# PW_portable.net
KiCad netlist of a schematic drawn in EAGLE
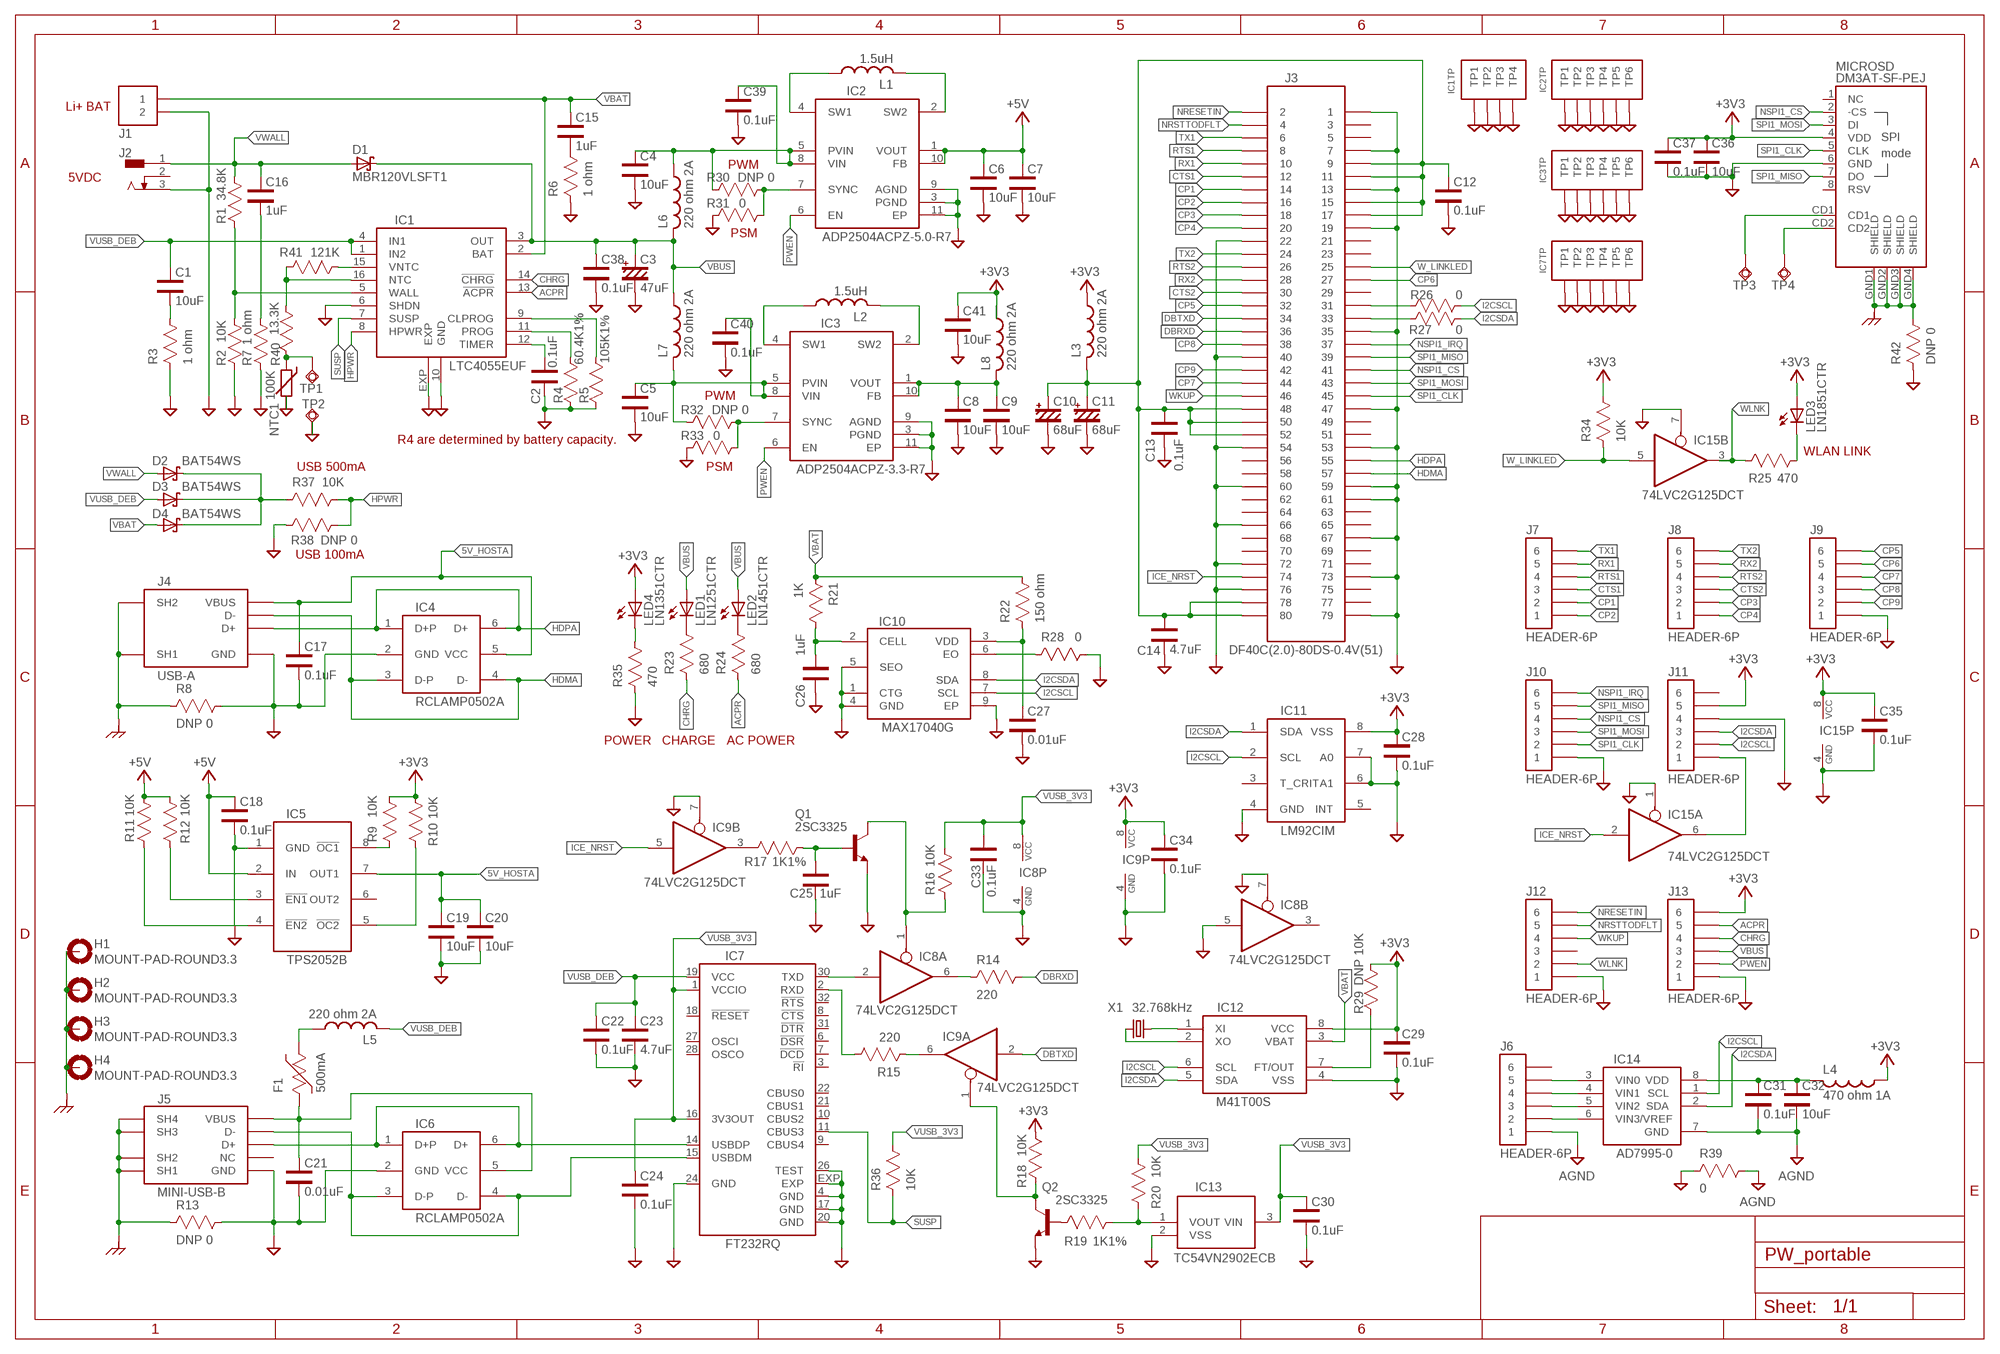
[diagram p0: schematic, sheet 1]

(export (version "E")
  (design (tool "Eeschema 10.0.6"))
  (components
    (comp (ref "C1")
      (value "10uF")
      (footprint "eagle-import:C0603")
      (libsource (lib "eagle-import") (part "C0603"))
    )
    (comp (ref "C2")
      (value "0.1uF")
      (footprint "eagle-import:C0603")
      (libsource (lib "eagle-import") (part "C0603"))
    )
    (comp (ref "C3")
      (value "47uF")
      (footprint "eagle-import:SMC_D")
      (libsource (lib "eagle-import") (part "CPSMC_D"))
    )
    (comp (ref "C4")
      (value "10uF")
      (footprint "eagle-import:C0603")
      (libsource (lib "eagle-import") (part "C0603"))
    )
    (comp (ref "C5")
      (value "10uF")
      (footprint "eagle-import:C0603")
      (libsource (lib "eagle-import") (part "C0603"))
    )
    (comp (ref "C6")
      (value "10uF")
      (footprint "eagle-import:C0603")
      (libsource (lib "eagle-import") (part "C0603"))
    )
    (comp (ref "C7")
      (value "10uF")
      (footprint "eagle-import:C0603")
      (libsource (lib "eagle-import") (part "C0603"))
    )
    (comp (ref "C8")
      (value "10uF")
      (footprint "eagle-import:C0603")
      (libsource (lib "eagle-import") (part "C0603"))
    )
    (comp (ref "C9")
      (value "10uF")
      (footprint "eagle-import:C0603")
      (libsource (lib "eagle-import") (part "C0603"))
    )
    (comp (ref "C10")
      (value "68uF")
      (footprint "eagle-import:SMC_D")
      (libsource (lib "eagle-import") (part "CPSMC_D"))
    )
    (comp (ref "C11")
      (value "68uF")
      (footprint "eagle-import:SMC_D")
      (libsource (lib "eagle-import") (part "CPSMC_D"))
    )
    (comp (ref "C12")
      (value "0.1uF")
      (footprint "eagle-import:C0603")
      (libsource (lib "eagle-import") (part "C0603"))
    )
    (comp (ref "C13")
      (value "0.1uF")
      (footprint "eagle-import:C0603")
      (libsource (lib "eagle-import") (part "C0603"))
    )
    (comp (ref "C14")
      (value "4.7uF")
      (footprint "eagle-import:C0603")
      (libsource (lib "eagle-import") (part "C0603"))
    )
    (comp (ref "C15")
      (value "1uF")
      (footprint "eagle-import:C0603")
      (libsource (lib "eagle-import") (part "C0603"))
    )
    (comp (ref "C16")
      (value "1uF")
      (footprint "eagle-import:C0603")
      (libsource (lib "eagle-import") (part "C0603"))
    )
    (comp (ref "C17")
      (value "0.1uF")
      (footprint "eagle-import:C0603")
      (libsource (lib "eagle-import") (part "C0603"))
    )
    (comp (ref "C18")
      (value "0.1uF")
      (footprint "eagle-import:C0603")
      (libsource (lib "eagle-import") (part "C0603"))
    )
    (comp (ref "C19")
      (value "10uF")
      (footprint "eagle-import:C0603")
      (libsource (lib "eagle-import") (part "C0603"))
    )
    (comp (ref "C20")
      (value "10uF")
      (footprint "eagle-import:C0603")
      (libsource (lib "eagle-import") (part "C0603"))
    )
    (comp (ref "C21")
      (value "0.01uF")
      (footprint "eagle-import:C0603")
      (libsource (lib "eagle-import") (part "C0603"))
    )
    (comp (ref "C22")
      (value "0.1uF")
      (footprint "eagle-import:C0603")
      (libsource (lib "eagle-import") (part "C0603"))
    )
    (comp (ref "C23")
      (value "4.7uF")
      (footprint "eagle-import:C0603")
      (libsource (lib "eagle-import") (part "C0603"))
    )
    (comp (ref "C24")
      (value "0.1uF")
      (footprint "eagle-import:C0603")
      (libsource (lib "eagle-import") (part "C0603"))
    )
    (comp (ref "C25")
      (value "1uF")
      (footprint "eagle-import:C0603")
      (libsource (lib "eagle-import") (part "C0603"))
    )
    (comp (ref "C26")
      (value "1uF")
      (footprint "eagle-import:C0603")
      (libsource (lib "eagle-import") (part "C0603"))
    )
    (comp (ref "C27")
      (value "0.01uF")
      (footprint "eagle-import:C0603")
      (libsource (lib "eagle-import") (part "C0603"))
    )
    (comp (ref "C28")
      (value "0.1uF")
      (footprint "eagle-import:C0603")
      (libsource (lib "eagle-import") (part "C0603"))
    )
    (comp (ref "C29")
      (value "0.1uF")
      (footprint "eagle-import:C0603")
      (libsource (lib "eagle-import") (part "C0603"))
    )
    (comp (ref "C30")
      (value "0.1uF")
      (footprint "eagle-import:C0603")
      (libsource (lib "eagle-import") (part "C0603"))
    )
    (comp (ref "C31")
      (value "0.1uF")
      (footprint "eagle-import:C0603")
      (libsource (lib "eagle-import") (part "C0603"))
    )
    (comp (ref "C32")
      (value "10uF")
      (footprint "eagle-import:C0603")
      (libsource (lib "eagle-import") (part "C0603"))
    )
    (comp (ref "C33")
      (value "0.1uF")
      (footprint "eagle-import:C0603")
      (libsource (lib "eagle-import") (part "C0603"))
    )
    (comp (ref "C34")
      (value "0.1uF")
      (footprint "eagle-import:C0603")
      (libsource (lib "eagle-import") (part "C0603"))
    )
    (comp (ref "C35")
      (value "0.1uF")
      (footprint "eagle-import:C0603")
      (libsource (lib "eagle-import") (part "C0603"))
    )
    (comp (ref "C36")
      (value "10uF")
      (footprint "eagle-import:C0603")
      (libsource (lib "eagle-import") (part "C0603"))
    )
    (comp (ref "C37")
      (value "0.1uF")
      (footprint "eagle-import:C0603")
      (libsource (lib "eagle-import") (part "C0603"))
    )
    (comp (ref "C38")
      (value "0.1uF")
      (footprint "eagle-import:C0603")
      (libsource (lib "eagle-import") (part "C0603"))
    )
    (comp (ref "C39")
      (value "0.1uF")
      (footprint "eagle-import:C0603")
      (libsource (lib "eagle-import") (part "C0603"))
    )
    (comp (ref "C40")
      (value "0.1uF")
      (footprint "eagle-import:C0603")
      (libsource (lib "eagle-import") (part "C0603"))
    )
    (comp (ref "C41")
      (value "10uF")
      (footprint "eagle-import:C0603")
      (libsource (lib "eagle-import") (part "C0603"))
    )
    (comp (ref "D1")
      (value "MBR120VLSFT1")
      (footprint "eagle-import:SOD123FL")
      (libsource (lib "eagle-import") (part "MBR120VLSFT1"))
    )
    (comp (ref "D2")
      (value "BAT54WS")
      (footprint "eagle-import:SOD323")
      (libsource (lib "eagle-import") (part "BAT54WS"))
    )
    (comp (ref "D3")
      (value "BAT54WS")
      (footprint "eagle-import:SOD323")
      (libsource (lib "eagle-import") (part "BAT54WS"))
    )
    (comp (ref "D4")
      (value "BAT54WS")
      (footprint "eagle-import:SOD323")
      (libsource (lib "eagle-import") (part "BAT54WS"))
    )
    (comp (ref "F1")
      (value "500mA")
      (footprint "eagle-import:P1206")
      (libsource (lib "eagle-import") (part "NANOSMDC050F/13"))
    )
    (comp (ref "H1")
      (value "MOUNT-PAD-ROUND3.3")
      (footprint "eagle-import:3,3-PAD")
      (libsource (lib "eagle-import") (part "MOUNT-PAD-ROUND3.3"))
    )
    (comp (ref "H2")
      (value "MOUNT-PAD-ROUND3.3")
      (footprint "eagle-import:3,3-PAD")
      (libsource (lib "eagle-import") (part "MOUNT-PAD-ROUND3.3"))
    )
    (comp (ref "H3")
      (value "MOUNT-PAD-ROUND3.3")
      (footprint "eagle-import:3,3-PAD")
      (libsource (lib "eagle-import") (part "MOUNT-PAD-ROUND3.3"))
    )
    (comp (ref "H4")
      (value "MOUNT-PAD-ROUND3.3")
      (footprint "eagle-import:3,3-PAD")
      (libsource (lib "eagle-import") (part "MOUNT-PAD-ROUND3.3"))
    )
    (comp (ref "IC1")
      (value "LTC4055EUF")
      (footprint "eagle-import:QFN16-4X4")
      (libsource (lib "eagle-import") (part "LTC4055EUF"))
    )
    (comp (ref "IC2")
      (value "ADP2504ACPZ-5.0-R7")
      (footprint "eagle-import:LFCSP_WD-CP-10-9")
      (libsource (lib "eagle-import") (part "ADP2504ACPZ-?-R75.0"))
    )
    (comp (ref "IC3")
      (value "ADP2504ACPZ-3.3-R7")
      (footprint "eagle-import:LFCSP_WD-CP-10-9")
      (libsource (lib "eagle-import") (part "ADP2504ACPZ-?-R73.3"))
    )
    (comp (ref "IC4")
      (value "RCLAMP0502A")
      (footprint "eagle-import:SOT666")
      (libsource (lib "eagle-import") (part "RCLAMP0502A"))
    )
    (comp (ref "IC5")
      (value "TPS2052B")
      (footprint "eagle-import:D_R-PDSO-G08")
      (libsource (lib "eagle-import") (part "TPS2052B"))
    )
    (comp (ref "IC6")
      (value "RCLAMP0502A")
      (footprint "eagle-import:SOT666")
      (libsource (lib "eagle-import") (part "RCLAMP0502A"))
    )
    (comp (ref "IC7")
      (value "FT232RQ")
      (footprint "eagle-import:QFN32")
      (libsource (lib "eagle-import") (part "FT232RQ"))
    )
    (comp (ref "IC8")
      (value "74LVC2G125DCT")
      (footprint "eagle-import:SSOP08")
      (libsource (lib "eagle-import") (part "742G125DCTLVC"))
    )
    (comp (ref "IC9")
      (value "74LVC2G125DCT")
      (footprint "eagle-import:SSOP08")
      (libsource (lib "eagle-import") (part "742G125DCTLVC"))
    )
    (comp (ref "IC10")
      (value "MAX17040G")
      (footprint "eagle-import:8-TDFN")
      (libsource (lib "eagle-import") (part "MAX17040G"))
    )
    (comp (ref "IC11")
      (value "LM92CIM")
      (footprint "eagle-import:SO08")
      (libsource (lib "eagle-import") (part "LM92CIM"))
    )
    (comp (ref "IC12")
      (value "M41T00S")
      (footprint "eagle-import:SO08")
      (libsource (lib "eagle-import") (part "M41T00S"))
    )
    (comp (ref "IC13")
      (value "TC54VN2902ECB")
      (footprint "eagle-import:SOT23")
      (libsource (lib "eagle-import") (part "TC54VN02E?CB29"))
    )
    (comp (ref "IC14")
      (value "AD7995-0")
      (footprint "eagle-import:SOT23-8")
      (libsource (lib "eagle-import") (part "AD799-05"))
    )
    (comp (ref "IC15")
      (value "74LVC2G125DCT")
      (footprint "eagle-import:SSOP08")
      (libsource (lib "eagle-import") (part "742G125DCTLVC"))
    )
    (comp (ref "J1")
      (value "JACK-JST-2P-PW'SMD'")
      (footprint "eagle-import:JST-SMD-2.0")
      (libsource (lib "eagle-import") (part "JACK-JST-2P-PW'SMD'"))
    )
    (comp (ref "J2")
      (value "DCJ0202")
      (footprint "eagle-import:DCJ0202")
      (libsource (lib "eagle-import") (part "DCJ0202"))
    )
    (comp (ref "J3")
      (value "DF40C(2.0)-80DS-0.4V(51)")
      (footprint "eagle-import:DF40C(2.0)-80DS-0.4V(51)")
      (libsource (lib "eagle-import") (part "DF40C(2.0)-80DS-0.4V(51)"))
    )
    (comp (ref "J4")
      (value "USB-A")
      (footprint "eagle-import:USB-A")
      (libsource (lib "eagle-import") (part "USB-AL"))
    )
    (comp (ref "J5")
      (value "MINI-USB-B")
      (footprint "eagle-import:1734035-2")
      (libsource (lib "eagle-import") (part "MINI-USB-B"))
    )
    (comp (ref "J6")
      (value "HEADER-6P")
      (footprint "eagle-import:6P-2.54")
      (libsource (lib "eagle-import") (part "HEADER-6P"))
    )
    (comp (ref "J7")
      (value "HEADER-6P")
      (footprint "eagle-import:6P-2.54")
      (libsource (lib "eagle-import") (part "HEADER-6P"))
    )
    (comp (ref "J8")
      (value "HEADER-6P")
      (footprint "eagle-import:6P-2.54")
      (libsource (lib "eagle-import") (part "HEADER-6P"))
    )
    (comp (ref "J9")
      (value "HEADER-6P")
      (footprint "eagle-import:6P-2.54")
      (libsource (lib "eagle-import") (part "HEADER-6P"))
    )
    (comp (ref "J10")
      (value "HEADER-6P")
      (footprint "eagle-import:6P-2.54")
      (libsource (lib "eagle-import") (part "HEADER-6P"))
    )
    (comp (ref "J11")
      (value "HEADER-6P")
      (footprint "eagle-import:6P-2.54")
      (libsource (lib "eagle-import") (part "HEADER-6P"))
    )
    (comp (ref "J12")
      (value "HEADER-6P")
      (footprint "eagle-import:6P-2.54")
      (libsource (lib "eagle-import") (part "HEADER-6P"))
    )
    (comp (ref "J13")
      (value "HEADER-6P")
      (footprint "eagle-import:6P-2.54")
      (libsource (lib "eagle-import") (part "HEADER-6P"))
    )
    (comp (ref "L1")
      (value "1.5uH")
      (footprint "eagle-import:L1008")
      (libsource (lib "eagle-import") (part "LQM2HPN1R5MG0L"))
    )
    (comp (ref "L2")
      (value "1.5uH")
      (footprint "eagle-import:L1008")
      (libsource (lib "eagle-import") (part "LQM2HPN1R5MG0L"))
    )
    (comp (ref "L3")
      (value "220 ohm 2A")
      (footprint "eagle-import:L0603")
      (libsource (lib "eagle-import") (part "BLM?PG18"))
    )
    (comp (ref "L4")
      (value "470 ohm 1A")
      (footprint "eagle-import:L0603")
      (libsource (lib "eagle-import") (part "BLM?PG18"))
    )
    (comp (ref "L5")
      (value "220 ohm 2A")
      (footprint "eagle-import:L0603")
      (libsource (lib "eagle-import") (part "BLM?PG18"))
    )
    (comp (ref "L6")
      (value "220 ohm 2A")
      (footprint "eagle-import:L0603")
      (libsource (lib "eagle-import") (part "BLM?PG18"))
    )
    (comp (ref "L7")
      (value "220 ohm 2A")
      (footprint "eagle-import:L0603")
      (libsource (lib "eagle-import") (part "BLM?PG18"))
    )
    (comp (ref "L8")
      (value "220 ohm 2A")
      (footprint "eagle-import:L0603")
      (libsource (lib "eagle-import") (part "BLM?PG18"))
    )
    (comp (ref "LED1")
      (value "LN1251CTR")
      (footprint "eagle-import:LED1208")
      (libsource (lib "eagle-import") (part "LN51CTR12"))
    )
    (comp (ref "LED2")
      (value "LN1451CTR")
      (footprint "eagle-import:LED1208")
      (libsource (lib "eagle-import") (part "LN51CTR14"))
    )
    (comp (ref "LED3")
      (value "LN1851CTR")
      (footprint "eagle-import:LED1208")
      (libsource (lib "eagle-import") (part "LN51CTR18"))
    )
    (comp (ref "LED4")
      (value "LN1351CTR")
      (footprint "eagle-import:LED1208")
      (libsource (lib "eagle-import") (part "LN51CTR13"))
    )
    (comp (ref "MICROSD")
      (value "DM3AT-SF-PEJ")
      (footprint "eagle-import:DM3AT-SF-PEJ")
      (libsource (lib "eagle-import") (part "DM3AT-SF-PEJ"))
    )
    (comp (ref "NTC1")
      (value "100K")
      (footprint "eagle-import:R0603")
      (libsource (lib "eagle-import") (part "NTHS0603"))
    )
    (comp (ref "Q1")
      (value "2SC3325")
      (footprint "eagle-import:SOT23-BEC")
      (libsource (lib "eagle-import") (part "2SC3325"))
    )
    (comp (ref "Q2")
      (value "2SC3325")
      (footprint "eagle-import:SOT23-BEC")
      (libsource (lib "eagle-import") (part "2SC3325"))
    )
    (comp (ref "R1")
      (value "34.8K")
      (footprint "eagle-import:R0603")
      (libsource (lib "eagle-import") (part "R0603"))
    )
    (comp (ref "R2")
      (value "10K")
      (footprint "eagle-import:R0603")
      (libsource (lib "eagle-import") (part "R0603"))
    )
    (comp (ref "R3")
      (value "1 ohm")
      (footprint "eagle-import:R0603")
      (libsource (lib "eagle-import") (part "R0603"))
    )
    (comp (ref "R4")
      (value "60.4K1%")
      (footprint "eagle-import:R0603")
      (libsource (lib "eagle-import") (part "R0603"))
    )
    (comp (ref "R5")
      (value "105K1%")
      (footprint "eagle-import:R0603")
      (libsource (lib "eagle-import") (part "R0603"))
    )
    (comp (ref "R6")
      (value "1 ohm")
      (footprint "eagle-import:R0603")
      (libsource (lib "eagle-import") (part "R0603"))
    )
    (comp (ref "R7")
      (value "1 ohm")
      (footprint "eagle-import:R0603")
      (libsource (lib "eagle-import") (part "R0603"))
    )
    (comp (ref "R8")
      (value "DNP 0")
      (footprint "eagle-import:R0603")
      (libsource (lib "eagle-import") (part "R0603"))
    )
    (comp (ref "R9")
      (value "10K")
      (footprint "eagle-import:R0603")
      (libsource (lib "eagle-import") (part "R0603"))
    )
    (comp (ref "R10")
      (value "10K")
      (footprint "eagle-import:R0603")
      (libsource (lib "eagle-import") (part "R0603"))
    )
    (comp (ref "R11")
      (value "10K")
      (footprint "eagle-import:R0603")
      (libsource (lib "eagle-import") (part "R0603"))
    )
    (comp (ref "R12")
      (value "10K")
      (footprint "eagle-import:R0603")
      (libsource (lib "eagle-import") (part "R0603"))
    )
    (comp (ref "R13")
      (value "DNP 0")
      (footprint "eagle-import:R0603")
      (libsource (lib "eagle-import") (part "R0603"))
    )
    (comp (ref "R14")
      (value "220")
      (footprint "eagle-import:R0603")
      (libsource (lib "eagle-import") (part "R0603"))
    )
    (comp (ref "R15")
      (value "220")
      (footprint "eagle-import:R0603")
      (libsource (lib "eagle-import") (part "R0603"))
    )
    (comp (ref "R16")
      (value "10K")
      (footprint "eagle-import:R0603")
      (libsource (lib "eagle-import") (part "R0603"))
    )
    (comp (ref "R17")
      (value "1K1%")
      (footprint "eagle-import:R0603")
      (libsource (lib "eagle-import") (part "R0603"))
    )
    (comp (ref "R18")
      (value "10K")
      (footprint "eagle-import:R0603")
      (libsource (lib "eagle-import") (part "R0603"))
    )
    (comp (ref "R19")
      (value "1K1%")
      (footprint "eagle-import:R0603")
      (libsource (lib "eagle-import") (part "R0603"))
    )
    (comp (ref "R20")
      (value "10K")
      (footprint "eagle-import:R0603")
      (libsource (lib "eagle-import") (part "R0603"))
    )
    (comp (ref "R21")
      (value "1K")
      (footprint "eagle-import:R0603")
      (libsource (lib "eagle-import") (part "R0603"))
    )
    (comp (ref "R22")
      (value "150 ohm")
      (footprint "eagle-import:R0603")
      (libsource (lib "eagle-import") (part "R0603"))
    )
    (comp (ref "R23")
      (value "680")
      (footprint "eagle-import:R0603")
      (libsource (lib "eagle-import") (part "R0603"))
    )
    (comp (ref "R24")
      (value "680")
      (footprint "eagle-import:R0603")
      (libsource (lib "eagle-import") (part "R0603"))
    )
    (comp (ref "R25")
      (value "470")
      (footprint "eagle-import:R0603")
      (libsource (lib "eagle-import") (part "R0603"))
    )
    (comp (ref "R26")
      (value "0")
      (footprint "eagle-import:R0603")
      (libsource (lib "eagle-import") (part "R0603"))
    )
    (comp (ref "R27")
      (value "0")
      (footprint "eagle-import:R0603")
      (libsource (lib "eagle-import") (part "R0603"))
    )
    (comp (ref "R28")
      (value "0")
      (footprint "eagle-import:R0603")
      (libsource (lib "eagle-import") (part "R0603"))
    )
    (comp (ref "R29")
      (value "DNP 10K")
      (footprint "eagle-import:R0603")
      (libsource (lib "eagle-import") (part "R0603"))
    )
    (comp (ref "R30")
      (value "DNP 0")
      (footprint "eagle-import:R0603")
      (libsource (lib "eagle-import") (part "R0603"))
    )
    (comp (ref "R31")
      (value "0")
      (footprint "eagle-import:R0603")
      (libsource (lib "eagle-import") (part "R0603"))
    )
    (comp (ref "R32")
      (value "DNP 0")
      (footprint "eagle-import:R0603")
      (libsource (lib "eagle-import") (part "R0603"))
    )
    (comp (ref "R33")
      (value "0")
      (footprint "eagle-import:R0603")
      (libsource (lib "eagle-import") (part "R0603"))
    )
    (comp (ref "R34")
      (value "10K")
      (footprint "eagle-import:R0603")
      (libsource (lib "eagle-import") (part "R0603"))
    )
    (comp (ref "R35")
      (value "470")
      (footprint "eagle-import:R0603")
      (libsource (lib "eagle-import") (part "R0603"))
    )
    (comp (ref "R36")
      (value "10K")
      (footprint "eagle-import:R0603")
      (libsource (lib "eagle-import") (part "R0603"))
    )
    (comp (ref "R37")
      (value "10K")
      (footprint "eagle-import:R0603")
      (libsource (lib "eagle-import") (part "R0603"))
    )
    (comp (ref "R38")
      (value "DNP 0")
      (footprint "eagle-import:R0603")
      (libsource (lib "eagle-import") (part "R0603"))
    )
    (comp (ref "R39")
      (value "0")
      (footprint "eagle-import:R0603")
      (libsource (lib "eagle-import") (part "R0603"))
    )
    (comp (ref "R40")
      (value "13.3K")
      (footprint "eagle-import:R0603")
      (libsource (lib "eagle-import") (part "R0603"))
    )
    (comp (ref "R41")
      (value "121K")
      (footprint "eagle-import:R0603")
      (libsource (lib "eagle-import") (part "R0603"))
    )
    (comp (ref "R42")
      (value "DNP 0")
      (footprint "eagle-import:R0603")
      (libsource (lib "eagle-import") (part "R0603"))
    )
    (comp (ref "TP1")
      (value "TPSQTP20SQ")
      (footprint "eagle-import:TP20SQ")
      (libsource (lib "eagle-import") (part "TPSQTP20SQ"))
    )
    (comp (ref "TP2")
      (value "TPSQTP20SQ")
      (footprint "eagle-import:TP20SQ")
      (libsource (lib "eagle-import") (part "TPSQTP20SQ"))
    )
    (comp (ref "TP3")
      (value "TPSQTP20SQ")
      (footprint "eagle-import:TP20SQ")
      (libsource (lib "eagle-import") (part "TPSQTP20SQ"))
    )
    (comp (ref "TP4")
      (value "TPSQTP20SQ")
      (footprint "eagle-import:TP20SQ")
      (libsource (lib "eagle-import") (part "TPSQTP20SQ"))
    )
    (comp (ref "X1")
      (value "32.768kHz")
      (footprint "eagle-import:FC255")
      (libsource (lib "eagle-import") (part "CRYSTALFC255"))
    )
  )
  (nets
    (net (code "1") (name "+3V3") (class "Default")
      (node (ref "C28") (pin "1") (pinfunction "1_1") (pintype "passive"))
      (node (ref "C29") (pin "1") (pinfunction "1_1") (pintype "passive"))
      (node (ref "C34") (pin "1") (pinfunction "1_1") (pintype "passive"))
      (node (ref "C35") (pin "1") (pinfunction "1_1") (pintype "passive"))
      (node (ref "C36") (pin "1") (pinfunction "1_1") (pintype "passive"))
      (node (ref "C37") (pin "1") (pinfunction "1_1") (pintype "passive"))
      (node (ref "C41") (pin "1") (pinfunction "1_1") (pintype "passive"))
      (node (ref "IC11") (pin "8") (pinfunction "VSS_8") (pintype "bidirectional"))
      (node (ref "IC12") (pin "8") (pinfunction "VCC_8") (pintype "bidirectional"))
      (node (ref "IC15") (pin "8") (pinfunction "VCC_8") (pintype "power_in"))
      (node (ref "IC9") (pin "8") (pinfunction "VCC_8") (pintype "power_in"))
      (node (ref "J11") (pin "5") (pinfunction "5_5") (pintype "bidirectional"))
      (node (ref "J13") (pin "6") (pinfunction "6_6") (pintype "bidirectional"))
      (node (ref "L3") (pin "1") (pinfunction "1_1") (pintype "passive"))
      (node (ref "L4") (pin "1") (pinfunction "1_1") (pintype "passive"))
      (node (ref "L8") (pin "1") (pinfunction "1_1") (pintype "passive"))
      (node (ref "LED3") (pin "A") (pinfunction "A_A") (pintype "passive"))
      (node (ref "LED4") (pin "A") (pinfunction "A_A") (pintype "passive"))
      (node (ref "MICROSD") (pin "4") (pinfunction "VDD_4") (pintype "bidirectional"))
      (node (ref "R10") (pin "2") (pinfunction "2_2") (pintype "passive"))
      (node (ref "R18") (pin "1") (pinfunction "1_1") (pintype "passive"))
      (node (ref "R29") (pin "2") (pinfunction "2_2") (pintype "passive"))
      (node (ref "R34") (pin "2") (pinfunction "2_2") (pintype "passive"))
      (node (ref "R9") (pin "2") (pinfunction "2_2") (pintype "passive"))
    )
    (net (code "2") (name "+5V") (class "Default")
      (node (ref "C18") (pin "1") (pinfunction "1_1") (pintype "passive"))
      (node (ref "C6") (pin "1") (pinfunction "1_1") (pintype "passive"))
      (node (ref "C7") (pin "1") (pinfunction "1_1") (pintype "passive"))
      (node (ref "IC2") (pin "1") (pinfunction "VOUT_1") (pintype "bidirectional"))
      (node (ref "IC2") (pin "10") (pinfunction "FB_10") (pintype "bidirectional"))
      (node (ref "IC5") (pin "2") (pinfunction "IN_2") (pintype "bidirectional"))
      (node (ref "R11") (pin "2") (pinfunction "2_2") (pintype "passive"))
      (node (ref "R12") (pin "2") (pinfunction "2_2") (pintype "passive"))
    )
    (net (code "3") (name "5V_HOSTA") (class "Default")
      (node (ref "C17") (pin "1") (pinfunction "1_1") (pintype "passive"))
      (node (ref "C19") (pin "1") (pinfunction "1_1") (pintype "passive"))
      (node (ref "C20") (pin "1") (pinfunction "1_1") (pintype "passive"))
      (node (ref "IC4") (pin "5") (pinfunction "VCC_5") (pintype "bidirectional"))
      (node (ref "IC5") (pin "7") (pinfunction "OUT1_7") (pintype "bidirectional"))
      (node (ref "J4") (pin "1") (pinfunction "VBUS_1") (pintype "passive"))
    )
    (net (code "4") (name "ACPR") (class "Default")
      (node (ref "IC1") (pin "13") (pinfunction "~{ACPR}_13") (pintype "bidirectional"))
      (node (ref "J13") (pin "5") (pinfunction "5_5") (pintype "bidirectional"))
      (node (ref "R24") (pin "1") (pinfunction "1_1") (pintype "passive"))
    )
    (net (code "5") (name "AGND") (class "Default")
      (node (ref "C31") (pin "2") (pinfunction "2_2") (pintype "passive"))
      (node (ref "C32") (pin "2") (pinfunction "2_2") (pintype "passive"))
      (node (ref "IC14") (pin "7") (pinfunction "GND_7") (pintype "bidirectional"))
      (node (ref "J6") (pin "1") (pinfunction "1_1") (pintype "bidirectional"))
      (node (ref "R39") (pin "2") (pinfunction "2_2") (pintype "passive"))
    )
    (net (code "6") (name "CHRG") (class "Default")
      (node (ref "IC1") (pin "14") (pinfunction "~{CHRG}_14") (pintype "bidirectional"))
      (node (ref "J13") (pin "4") (pinfunction "4_4") (pintype "bidirectional"))
      (node (ref "R23") (pin "1") (pinfunction "1_1") (pintype "passive"))
    )
    (net (code "7") (name "CP1") (class "Default")
      (node (ref "J3") (pin "14") (pinfunction "14_14") (pintype "bidirectional"))
      (node (ref "J7") (pin "2") (pinfunction "2_2") (pintype "bidirectional"))
    )
    (net (code "8") (name "CP2") (class "Default")
      (node (ref "J3") (pin "16") (pinfunction "16_16") (pintype "bidirectional"))
      (node (ref "J7") (pin "1") (pinfunction "1_1") (pintype "bidirectional"))
    )
    (net (code "9") (name "CP3") (class "Default")
      (node (ref "J3") (pin "18") (pinfunction "18_18") (pintype "bidirectional"))
      (node (ref "J8") (pin "2") (pinfunction "2_2") (pintype "bidirectional"))
    )
    (net (code "10") (name "CP4") (class "Default")
      (node (ref "J3") (pin "20") (pinfunction "20_20") (pintype "bidirectional"))
      (node (ref "J8") (pin "1") (pinfunction "1_1") (pintype "bidirectional"))
    )
    (net (code "11") (name "CP5") (class "Default")
      (node (ref "J3") (pin "32") (pinfunction "32_32") (pintype "bidirectional"))
      (node (ref "J9") (pin "6") (pinfunction "6_6") (pintype "bidirectional"))
    )
    (net (code "12") (name "CP6") (class "Default")
      (node (ref "J3") (pin "27") (pinfunction "27_27") (pintype "bidirectional"))
      (node (ref "J9") (pin "5") (pinfunction "5_5") (pintype "bidirectional"))
    )
    (net (code "13") (name "CP7") (class "Default")
      (node (ref "J3") (pin "44") (pinfunction "44_44") (pintype "bidirectional"))
      (node (ref "J9") (pin "4") (pinfunction "4_4") (pintype "bidirectional"))
    )
    (net (code "14") (name "CP8") (class "Default")
      (node (ref "J3") (pin "38") (pinfunction "38_38") (pintype "bidirectional"))
      (node (ref "J9") (pin "3") (pinfunction "3_3") (pintype "bidirectional"))
    )
    (net (code "15") (name "CP9") (class "Default")
      (node (ref "J3") (pin "42") (pinfunction "42_42") (pintype "bidirectional"))
      (node (ref "J9") (pin "2") (pinfunction "2_2") (pintype "bidirectional"))
    )
    (net (code "16") (name "CTS1") (class "Default")
      (node (ref "J3") (pin "12") (pinfunction "12_12") (pintype "bidirectional"))
      (node (ref "J7") (pin "3") (pinfunction "3_3") (pintype "bidirectional"))
    )
    (net (code "17") (name "CTS2") (class "Default")
      (node (ref "J3") (pin "30") (pinfunction "30_30") (pintype "bidirectional"))
      (node (ref "J8") (pin "3") (pinfunction "3_3") (pintype "bidirectional"))
    )
    (net (code "18") (name "DBRXD") (class "Default")
      (node (ref "J3") (pin "36") (pinfunction "36_36") (pintype "bidirectional"))
      (node (ref "R14") (pin "2") (pinfunction "2_2") (pintype "passive"))
    )
    (net (code "19") (name "DBTXD") (class "Default")
      (node (ref "IC9") (pin "2") (pinfunction "I_2") (pintype "input"))
      (node (ref "J3") (pin "34") (pinfunction "34_34") (pintype "bidirectional"))
    )
    (net (code "20") (name "DGND") (class "Default")
      (node (ref "C10") (pin "-") (pinfunction "-_-") (pintype "passive"))
      (node (ref "C11") (pin "-") (pinfunction "-_-") (pintype "passive"))
      (node (ref "C12") (pin "2") (pinfunction "2_2") (pintype "passive"))
      (node (ref "C13") (pin "2") (pinfunction "2_2") (pintype "passive"))
      (node (ref "C14") (pin "2") (pinfunction "2_2") (pintype "passive"))
      (node (ref "C17") (pin "2") (pinfunction "2_2") (pintype "passive"))
      (node (ref "C18") (pin "2") (pinfunction "2_2") (pintype "passive"))
      (node (ref "C19") (pin "2") (pinfunction "2_2") (pintype "passive"))
      (node (ref "C2") (pin "2") (pinfunction "2_2") (pintype "passive"))
      (node (ref "C20") (pin "2") (pinfunction "2_2") (pintype "passive"))
      (node (ref "C21") (pin "2") (pinfunction "2_2") (pintype "passive"))
      (node (ref "C22") (pin "2") (pinfunction "2_2") (pintype "passive"))
      (node (ref "C23") (pin "2") (pinfunction "2_2") (pintype "passive"))
      (node (ref "C24") (pin "2") (pinfunction "2_2") (pintype "passive"))
      (node (ref "C25") (pin "2") (pinfunction "2_2") (pintype "passive"))
      (node (ref "C26") (pin "2") (pinfunction "2_2") (pintype "passive"))
      (node (ref "C27") (pin "2") (pinfunction "2_2") (pintype "passive"))
      (node (ref "C28") (pin "2") (pinfunction "2_2") (pintype "passive"))
      (node (ref "C29") (pin "2") (pinfunction "2_2") (pintype "passive"))
      (node (ref "C3") (pin "-") (pinfunction "-_-") (pintype "passive"))
      (node (ref "C30") (pin "2") (pinfunction "2_2") (pintype "passive"))
      (node (ref "C33") (pin "2") (pinfunction "2_2") (pintype "passive"))
      (node (ref "C34") (pin "2") (pinfunction "2_2") (pintype "passive"))
      (node (ref "C35") (pin "2") (pinfunction "2_2") (pintype "passive"))
      (node (ref "C36") (pin "2") (pinfunction "2_2") (pintype "passive"))
      (node (ref "C37") (pin "2") (pinfunction "2_2") (pintype "passive"))
      (node (ref "C38") (pin "2") (pinfunction "2_2") (pintype "passive"))
      (node (ref "C39") (pin "2") (pinfunction "2_2") (pintype "passive"))
      (node (ref "C4") (pin "2") (pinfunction "2_2") (pintype "passive"))
      (node (ref "C40") (pin "2") (pinfunction "2_2") (pintype "passive"))
      (node (ref "C41") (pin "2") (pinfunction "2_2") (pintype "passive"))
      (node (ref "C5") (pin "2") (pinfunction "2_2") (pintype "passive"))
      (node (ref "C6") (pin "2") (pinfunction "2_2") (pintype "passive"))
      (node (ref "C7") (pin "2") (pinfunction "2_2") (pintype "passive"))
      (node (ref "C8") (pin "2") (pinfunction "2_2") (pintype "passive"))
      (node (ref "C9") (pin "2") (pinfunction "2_2") (pintype "passive"))
      (node (ref "IC1") (pin "10") (pinfunction "GND_10") (pintype "bidirectional"))
      (node (ref "IC1") (pin "6") (pinfunction "SHDN_6") (pintype "bidirectional"))
      (node (ref "IC1") (pin "EXP") (pinfunction "EXP_EXP") (pintype "bidirectional"))
      (node (ref "IC1") (pin "P$1") (pinfunction "TP1_P$1") (pintype "passive"))
      (node (ref "IC1") (pin "P$2") (pinfunction "TP2_P$2") (pintype "passive"))
      (node (ref "IC1") (pin "P$3") (pinfunction "TP3_P$3") (pintype "passive"))
      (node (ref "IC1") (pin "P$4") (pinfunction "TP4_P$4") (pintype "passive"))
      (node (ref "IC10") (pin "1") (pinfunction "CTG_1") (pintype "bidirectional"))
      (node (ref "IC10") (pin "4") (pinfunction "GND_4") (pintype "bidirectional"))
      (node (ref "IC10") (pin "5") (pinfunction "SEO_5") (pintype "bidirectional"))
      (node (ref "IC10") (pin "9") (pinfunction "EP_9") (pintype "bidirectional"))
      (node (ref "IC11") (pin "4") (pinfunction "GND_4") (pintype "bidirectional"))
      (node (ref "IC11") (pin "6") (pinfunction "A1_6") (pintype "bidirectional"))
      (node (ref "IC11") (pin "7") (pinfunction "A0_7") (pintype "bidirectional"))
      (node (ref "IC12") (pin "4") (pinfunction "VSS_4") (pintype "bidirectional"))
      (node (ref "IC13") (pin "2") (pinfunction "VSS_2") (pintype "bidirectional"))
      (node (ref "IC15") (pin "1") (pinfunction "OE_1") (pintype "input"))
      (node (ref "IC15") (pin "4") (pinfunction "GND_4") (pintype "power_in"))
      (node (ref "IC15") (pin "7") (pinfunction "OE_7") (pintype "input"))
      (node (ref "IC2") (pin "11") (pinfunction "EP_11") (pintype "bidirectional"))
      (node (ref "IC2") (pin "3") (pinfunction "PGND_3") (pintype "bidirectional"))
      (node (ref "IC2") (pin "9") (pinfunction "AGND_9") (pintype "bidirectional"))
      (node (ref "IC2") (pin "P$1") (pinfunction "TP1_P$1") (pintype "passive"))
      (node (ref "IC2") (pin "P$2") (pinfunction "TP2_P$2") (pintype "passive"))
      (node (ref "IC2") (pin "P$3") (pinfunction "TP3_P$3") (pintype "passive"))
      (node (ref "IC2") (pin "P$4") (pinfunction "TP4_P$4") (pintype "passive"))
      (node (ref "IC2") (pin "P$5") (pinfunction "TP5_P$5") (pintype "passive"))
      (node (ref "IC2") (pin "P$6") (pinfunction "TP6_P$6") (pintype "passive"))
      (node (ref "IC3") (pin "11") (pinfunction "EP_11") (pintype "bidirectional"))
      (node (ref "IC3") (pin "3") (pinfunction "PGND_3") (pintype "bidirectional"))
      (node (ref "IC3") (pin "9") (pinfunction "AGND_9") (pintype "bidirectional"))
      (node (ref "IC3") (pin "P$1") (pinfunction "TP1_P$1") (pintype "passive"))
      (node (ref "IC3") (pin "P$2") (pinfunction "TP2_P$2") (pintype "passive"))
      (node (ref "IC3") (pin "P$3") (pinfunction "TP3_P$3") (pintype "passive"))
      (node (ref "IC3") (pin "P$4") (pinfunction "TP4_P$4") (pintype "passive"))
      (node (ref "IC3") (pin "P$5") (pinfunction "TP5_P$5") (pintype "passive"))
      (node (ref "IC3") (pin "P$6") (pinfunction "TP6_P$6") (pintype "passive"))
      (node (ref "IC4") (pin "2") (pinfunction "GND_2") (pintype "bidirectional"))
      (node (ref "IC5") (pin "1") (pinfunction "GND_1") (pintype "bidirectional"))
      (node (ref "IC6") (pin "2") (pinfunction "GND_2") (pintype "bidirectional"))
      (node (ref "IC7") (pin "17") (pinfunction "GND_17") (pintype "power_in"))
      (node (ref "IC7") (pin "20") (pinfunction "GND_20") (pintype "power_in"))
      (node (ref "IC7") (pin "24") (pinfunction "GND_24") (pintype "power_in"))
      (node (ref "IC7") (pin "26") (pinfunction "TEST_26") (pintype "input"))
      (node (ref "IC7") (pin "4") (pinfunction "GND_4") (pintype "power_in"))
      (node (ref "IC7") (pin "EXP") (pinfunction "EXP_EXP") (pintype "bidirectional"))
      (node (ref "IC7") (pin "P$1") (pinfunction "TP1_P$1") (pintype "passive"))
      (node (ref "IC7") (pin "P$2") (pinfunction "TP2_P$2") (pintype "passive"))
      (node (ref "IC7") (pin "P$3") (pinfunction "TP3_P$3") (pintype "passive"))
      (node (ref "IC7") (pin "P$4") (pinfunction "TP4_P$4") (pintype "passive"))
      (node (ref "IC7") (pin "P$5") (pinfunction "TP5_P$5") (pintype "passive"))
      (node (ref "IC7") (pin "P$6") (pinfunction "TP6_P$6") (pintype "passive"))
      (node (ref "IC8") (pin "4") (pinfunction "GND_4") (pintype "power_in"))
      (node (ref "IC8") (pin "5") (pinfunction "I_5") (pintype "input"))
      (node (ref "IC8") (pin "7") (pinfunction "OE_7") (pintype "input"))
      (node (ref "IC9") (pin "4") (pinfunction "GND_4") (pintype "power_in"))
      (node (ref "IC9") (pin "7") (pinfunction "OE_7") (pintype "input"))
      (node (ref "J1") (pin "2") (pinfunction "2_2") (pintype "bidirectional"))
      (node (ref "J10") (pin "1") (pinfunction "1_1") (pintype "bidirectional"))
      (node (ref "J11") (pin "4") (pinfunction "4_4") (pintype "bidirectional"))
      (node (ref "J12") (pin "1") (pinfunction "1_1") (pintype "bidirectional"))
      (node (ref "J13") (pin "1") (pinfunction "1_1") (pintype "bidirectional"))
      (node (ref "J2") (pin "3") (pinfunction "3_3") (pintype "passive"))
      (node (ref "J3") (pin "1") (pinfunction "1_1") (pintype "bidirectional"))
      (node (ref "J3") (pin "13") (pinfunction "13_13") (pintype "bidirectional"))
      (node (ref "J3") (pin "19") (pinfunction "19_19") (pintype "bidirectional"))
      (node (ref "J3") (pin "22") (pinfunction "22_22") (pintype "bidirectional"))
      (node (ref "J3") (pin "35") (pinfunction "35_35") (pintype "bidirectional"))
      (node (ref "J3") (pin "40") (pinfunction "40_40") (pintype "bidirectional"))
      (node (ref "J3") (pin "47") (pinfunction "47_47") (pintype "bidirectional"))
      (node (ref "J3") (pin "53") (pinfunction "53_53") (pintype "bidirectional"))
      (node (ref "J3") (pin "54") (pinfunction "54_54") (pintype "bidirectional"))
      (node (ref "J3") (pin "59") (pinfunction "59_59") (pintype "bidirectional"))
      (node (ref "J3") (pin "60") (pinfunction "60_60") (pintype "bidirectional"))
      (node (ref "J3") (pin "61") (pinfunction "61_61") (pintype "bidirectional"))
      (node (ref "J3") (pin "66") (pinfunction "66_66") (pintype "bidirectional"))
      (node (ref "J3") (pin "67") (pinfunction "67_67") (pintype "bidirectional"))
      (node (ref "J3") (pin "7") (pinfunction "7_7") (pintype "bidirectional"))
      (node (ref "J3") (pin "72") (pinfunction "72_72") (pintype "bidirectional"))
      (node (ref "J3") (pin "73") (pinfunction "73_73") (pintype "bidirectional"))
      (node (ref "J3") (pin "76") (pinfunction "76_76") (pintype "bidirectional"))
      (node (ref "J3") (pin "79") (pinfunction "79_79") (pintype "bidirectional"))
      (node (ref "J4") (pin "4") (pinfunction "GND_4") (pintype "passive"))
      (node (ref "J5") (pin "5") (pinfunction "GND_5") (pintype "passive"))
      (node (ref "J9") (pin "1") (pinfunction "1_1") (pintype "bidirectional"))
      (node (ref "MICROSD") (pin "6") (pinfunction "GND_6") (pintype "bidirectional"))
      (node (ref "NTC1") (pin "2") (pinfunction "2_2") (pintype "passive"))
      (node (ref "Q1") (pin "E") (pinfunction "E_E") (pintype "passive"))
      (node (ref "Q2") (pin "E") (pinfunction "E_E") (pintype "passive"))
      (node (ref "R13") (pin "2") (pinfunction "2_2") (pintype "passive"))
      (node (ref "R2") (pin "1") (pinfunction "1_1") (pintype "passive"))
      (node (ref "R28") (pin "2") (pinfunction "2_2") (pintype "passive"))
      (node (ref "R3") (pin "1") (pinfunction "1_1") (pintype "passive"))
      (node (ref "R31") (pin "1") (pinfunction "1_1") (pintype "passive"))
      (node (ref "R33") (pin "1") (pinfunction "1_1") (pintype "passive"))
      (node (ref "R35") (pin "1") (pinfunction "1_1") (pintype "passive"))
      (node (ref "R38") (pin "1") (pinfunction "1_1") (pintype "passive"))
      (node (ref "R39") (pin "1") (pinfunction "1_1") (pintype "passive"))
      (node (ref "R4") (pin "1") (pinfunction "1_1") (pintype "passive"))
      (node (ref "R42") (pin "1") (pinfunction "1_1") (pintype "passive"))
      (node (ref "R5") (pin "1") (pinfunction "1_1") (pintype "passive"))
      (node (ref "R6") (pin "1") (pinfunction "1_1") (pintype "passive"))
      (node (ref "R7") (pin "1") (pinfunction "1_1") (pintype "passive"))
      (node (ref "R8") (pin "2") (pinfunction "2_2") (pintype "passive"))
      (node (ref "TP2") (pin "TP") (pinfunction "TP_TP") (pintype "input"))
    )
    (net (code "21") (name "EGND") (class "Default")
      (node (ref "H1") (pin "B3,3") (pinfunction "MOUNT_B3,3") (pintype "passive"))
      (node (ref "H2") (pin "B3,3") (pinfunction "MOUNT_B3,3") (pintype "passive"))
      (node (ref "H3") (pin "B3,3") (pinfunction "MOUNT_B3,3") (pintype "passive"))
      (node (ref "H4") (pin "B3,3") (pinfunction "MOUNT_B3,3") (pintype "passive"))
      (node (ref "J4") (pin "5") (pinfunction "SH1_5") (pintype "passive"))
      (node (ref "J4") (pin "6") (pinfunction "SH2_6") (pintype "passive"))
      (node (ref "J5") (pin "M1") (pinfunction "SH1_M1") (pintype "passive"))
      (node (ref "J5") (pin "M2") (pinfunction "SH2_M2") (pintype "passive"))
      (node (ref "J5") (pin "M3") (pinfunction "SH3_M3") (pintype "passive"))
      (node (ref "J5") (pin "M4") (pinfunction "SH4_M4") (pintype "passive"))
      (node (ref "MICROSD") (pin "GND1") (pinfunction "SHIELD_GND1") (pintype "bidirectional"))
      (node (ref "MICROSD") (pin "GND2") (pinfunction "SHIELD_GND2") (pintype "bidirectional"))
      (node (ref "MICROSD") (pin "GND3") (pinfunction "SHIELD_GND3") (pintype "bidirectional"))
      (node (ref "MICROSD") (pin "GND4") (pinfunction "SHIELD_GND4") (pintype "bidirectional"))
      (node (ref "R13") (pin "1") (pinfunction "1_1") (pintype "passive"))
      (node (ref "R42") (pin "2") (pinfunction "2_2") (pintype "passive"))
      (node (ref "R8") (pin "1") (pinfunction "1_1") (pintype "passive"))
    )
    (net (code "22") (name "HDMA") (class "Default")
      (node (ref "IC4") (pin "3") (pinfunction "D-P_3") (pintype "bidirectional"))
      (node (ref "IC4") (pin "4") (pinfunction "D-_4") (pintype "bidirectional"))
      (node (ref "J3") (pin "57") (pinfunction "57_57") (pintype "bidirectional"))
      (node (ref "J4") (pin "2") (pinfunction "D-_2") (pintype "passive"))
    )
    (net (code "23") (name "HDPA") (class "Default")
      (node (ref "IC4") (pin "1") (pinfunction "D+P_1") (pintype "bidirectional"))
      (node (ref "IC4") (pin "6") (pinfunction "D+_6") (pintype "bidirectional"))
      (node (ref "J3") (pin "55") (pinfunction "55_55") (pintype "bidirectional"))
      (node (ref "J4") (pin "3") (pinfunction "D+_3") (pintype "passive"))
    )
    (net (code "24") (name "HPWR") (class "Default")
      (node (ref "IC1") (pin "8") (pinfunction "HPWR_8") (pintype "bidirectional"))
      (node (ref "R37") (pin "2") (pinfunction "2_2") (pintype "passive"))
      (node (ref "R38") (pin "2") (pinfunction "2_2") (pintype "passive"))
    )
    (net (code "25") (name "I2CSCL") (class "Default")
      (node (ref "IC10") (pin "7") (pinfunction "SCL_7") (pintype "bidirectional"))
      (node (ref "IC11") (pin "2") (pinfunction "SCL_2") (pintype "bidirectional"))
      (node (ref "IC12") (pin "6") (pinfunction "SCL_6") (pintype "bidirectional"))
      (node (ref "IC14") (pin "1") (pinfunction "SCL_1") (pintype "bidirectional"))
      (node (ref "J11") (pin "2") (pinfunction "2_2") (pintype "bidirectional"))
      (node (ref "R26") (pin "2") (pinfunction "2_2") (pintype "passive"))
    )
    (net (code "26") (name "I2CSDA") (class "Default")
      (node (ref "IC10") (pin "8") (pinfunction "SDA_8") (pintype "bidirectional"))
      (node (ref "IC11") (pin "1") (pinfunction "SDA_1") (pintype "bidirectional"))
      (node (ref "IC12") (pin "5") (pinfunction "SDA_5") (pintype "bidirectional"))
      (node (ref "IC14") (pin "2") (pinfunction "SDA_2") (pintype "bidirectional"))
      (node (ref "J11") (pin "3") (pinfunction "3_3") (pintype "bidirectional"))
      (node (ref "R27") (pin "2") (pinfunction "2_2") (pintype "passive"))
    )
    (net (code "27") (name "ICE_NRST") (class "Default")
      (node (ref "IC15") (pin "2") (pinfunction "I_2") (pintype "input"))
      (node (ref "IC9") (pin "5") (pinfunction "I_5") (pintype "input"))
      (node (ref "J3") (pin "74") (pinfunction "74_74") (pintype "bidirectional"))
    )
    (net (code "28") (name "NRESETIN") (class "Default")
      (node (ref "J12") (pin "6") (pinfunction "6_6") (pintype "bidirectional"))
      (node (ref "J3") (pin "2") (pinfunction "2_2") (pintype "bidirectional"))
    )
    (net (code "29") (name "NRSTTODFLT") (class "Default")
      (node (ref "J12") (pin "5") (pinfunction "5_5") (pintype "bidirectional"))
      (node (ref "J3") (pin "4") (pinfunction "4_4") (pintype "bidirectional"))
    )
    (net (code "30") (name "NSPI1_CS") (class "Default")
      (node (ref "J10") (pin "4") (pinfunction "4_4") (pintype "bidirectional"))
      (node (ref "J3") (pin "41") (pinfunction "41_41") (pintype "bidirectional"))
      (node (ref "MICROSD") (pin "2") (pinfunction "-CS_2") (pintype "bidirectional"))
    )
    (net (code "31") (name "NSPI1_IRQ") (class "Default")
      (node (ref "J10") (pin "6") (pinfunction "6_6") (pintype "bidirectional"))
      (node (ref "J3") (pin "37") (pinfunction "37_37") (pintype "bidirectional"))
    )
    (net (code "32") (name "Net-(C1-Pad2)") (class "Default")
      (node (ref "C1") (pin "2") (pinfunction "2_2") (pintype "passive"))
      (node (ref "R3") (pin "2") (pinfunction "2_2") (pintype "passive"))
    )
    (net (code "33") (name "Net-(C10-Pad+)") (class "Default")
      (node (ref "C10") (pin "+") (pinfunction "+_+") (pintype "passive"))
      (node (ref "C11") (pin "+") (pinfunction "+_+") (pintype "passive"))
      (node (ref "C12") (pin "1") (pinfunction "1_1") (pintype "passive"))
      (node (ref "C13") (pin "1") (pinfunction "1_1") (pintype "passive"))
      (node (ref "C14") (pin "1") (pinfunction "1_1") (pintype "passive"))
      (node (ref "J3") (pin "11") (pinfunction "11_11") (pintype "bidirectional"))
      (node (ref "J3") (pin "15") (pinfunction "15_15") (pintype "bidirectional"))
      (node (ref "J3") (pin "17") (pinfunction "17_17") (pintype "bidirectional"))
      (node (ref "J3") (pin "48") (pinfunction "48_48") (pintype "bidirectional"))
      (node (ref "J3") (pin "50") (pinfunction "50_50") (pintype "bidirectional"))
      (node (ref "J3") (pin "52") (pinfunction "52_52") (pintype "bidirectional"))
      (node (ref "J3") (pin "78") (pinfunction "78_78") (pintype "bidirectional"))
      (node (ref "J3") (pin "80") (pinfunction "80_80") (pintype "bidirectional"))
      (node (ref "J3") (pin "9") (pinfunction "9_9") (pintype "bidirectional"))
      (node (ref "L3") (pin "2") (pinfunction "2_2") (pintype "passive"))
    )
    (net (code "34") (name "Net-(C15-Pad2)") (class "Default")
      (node (ref "C15") (pin "2") (pinfunction "2_2") (pintype "passive"))
      (node (ref "R6") (pin "2") (pinfunction "2_2") (pintype "passive"))
    )
    (net (code "35") (name "Net-(C16-Pad2)") (class "Default")
      (node (ref "C16") (pin "2") (pinfunction "2_2") (pintype "passive"))
      (node (ref "R7") (pin "2") (pinfunction "2_2") (pintype "passive"))
    )
    (net (code "36") (name "Net-(C25-Pad1)") (class "Default")
      (node (ref "C25") (pin "1") (pinfunction "1_1") (pintype "passive"))
      (node (ref "Q1") (pin "B") (pinfunction "B_B") (pintype "passive"))
      (node (ref "R17") (pin "1") (pinfunction "1_1") (pintype "passive"))
    )
    (net (code "37") (name "Net-(D2-PadC)") (class "Default")
      (node (ref "D2") (pin "C") (pinfunction "C_C") (pintype "passive"))
      (node (ref "D3") (pin "C") (pinfunction "C_C") (pintype "passive"))
      (node (ref "D4") (pin "C") (pinfunction "C_C") (pintype "passive"))
      (node (ref "R37") (pin "1") (pinfunction "1_1") (pintype "passive"))
    )
    (net (code "38") (name "Net-(F1-Pad2)") (class "Default")
      (node (ref "F1") (pin "2") (pinfunction "2_2") (pintype "passive"))
      (node (ref "L5") (pin "1") (pinfunction "1_1") (pintype "passive"))
    )
    (net (code "39") (name "Net-(IC1A-CLPROG)") (class "Default")
      (node (ref "IC1") (pin "9") (pinfunction "CLPROG_9") (pintype "bidirectional"))
      (node (ref "R5") (pin "2") (pinfunction "2_2") (pintype "passive"))
    )
    (net (code "40") (name "Net-(IC1A-NTC)") (class "Default")
      (node (ref "IC1") (pin "16") (pinfunction "NTC_16") (pintype "bidirectional"))
      (node (ref "R40") (pin "2") (pinfunction "2_2") (pintype "passive"))
      (node (ref "R41") (pin "2") (pinfunction "2_2") (pintype "passive"))
    )
    (net (code "41") (name "Net-(IC1A-PROG)") (class "Default")
      (node (ref "IC1") (pin "11") (pinfunction "PROG_11") (pintype "bidirectional"))
      (node (ref "R4") (pin "2") (pinfunction "2_2") (pintype "passive"))
    )
    (net (code "42") (name "Net-(IC1A-TIMER)") (class "Default")
      (node (ref "C2") (pin "1") (pinfunction "1_1") (pintype "passive"))
      (node (ref "IC1") (pin "12") (pinfunction "TIMER_12") (pintype "bidirectional"))
    )
    (net (code "43") (name "Net-(IC1A-VNTC)") (class "Default")
      (node (ref "IC1") (pin "15") (pinfunction "VNTC_15") (pintype "bidirectional"))
      (node (ref "R41") (pin "1") (pinfunction "1_1") (pintype "passive"))
    )
    (net (code "44") (name "Net-(IC1A-WALL)") (class "Default")
      (node (ref "IC1") (pin "5") (pinfunction "WALL_5") (pintype "bidirectional"))
      (node (ref "R1") (pin "1") (pinfunction "1_1") (pintype "passive"))
      (node (ref "R2") (pin "2") (pinfunction "2_2") (pintype "passive"))
    )
    (net (code "45") (name "Net-(IC2A-PVIN)") (class "Default")
      (node (ref "C39") (pin "1") (pinfunction "1_1") (pintype "passive"))
      (node (ref "C4") (pin "1") (pinfunction "1_1") (pintype "passive"))
      (node (ref "IC2") (pin "5") (pinfunction "PVIN_5") (pintype "bidirectional"))
      (node (ref "IC2") (pin "8") (pinfunction "VIN_8") (pintype "bidirectional"))
      (node (ref "L6") (pin "1") (pinfunction "1_1") (pintype "passive"))
      (node (ref "R30") (pin "1") (pinfunction "1_1") (pintype "passive"))
    )
    (net (code "46") (name "Net-(IC2A-SW1)") (class "Default")
      (node (ref "IC2") (pin "4") (pinfunction "SW1_4") (pintype "bidirectional"))
      (node (ref "L1") (pin "1") (pinfunction "1_1") (pintype "passive"))
    )
    (net (code "47") (name "Net-(IC2A-SW2)") (class "Default")
      (node (ref "IC2") (pin "2") (pinfunction "SW2_2") (pintype "bidirectional"))
      (node (ref "L1") (pin "2") (pinfunction "2_2") (pintype "passive"))
    )
    (net (code "48") (name "Net-(IC2A-SYNC)") (class "Default")
      (node (ref "IC2") (pin "7") (pinfunction "SYNC_7") (pintype "bidirectional"))
      (node (ref "R30") (pin "2") (pinfunction "2_2") (pintype "passive"))
      (node (ref "R31") (pin "2") (pinfunction "2_2") (pintype "passive"))
    )
    (net (code "49") (name "Net-(IC3A-FB)") (class "Default")
      (node (ref "C8") (pin "1") (pinfunction "1_1") (pintype "passive"))
      (node (ref "C9") (pin "1") (pinfunction "1_1") (pintype "passive"))
      (node (ref "IC3") (pin "1") (pinfunction "VOUT_1") (pintype "bidirectional"))
      (node (ref "IC3") (pin "10") (pinfunction "FB_10") (pintype "bidirectional"))
      (node (ref "L8") (pin "2") (pinfunction "2_2") (pintype "passive"))
    )
    (net (code "50") (name "Net-(IC3A-PVIN)") (class "Default")
      (node (ref "C40") (pin "1") (pinfunction "1_1") (pintype "passive"))
      (node (ref "C5") (pin "1") (pinfunction "1_1") (pintype "passive"))
      (node (ref "IC3") (pin "5") (pinfunction "PVIN_5") (pintype "bidirectional"))
      (node (ref "IC3") (pin "8") (pinfunction "VIN_8") (pintype "bidirectional"))
      (node (ref "L7") (pin "2") (pinfunction "2_2") (pintype "passive"))
      (node (ref "R32") (pin "1") (pinfunction "1_1") (pintype "passive"))
    )
    (net (code "51") (name "Net-(IC3A-SW1)") (class "Default")
      (node (ref "IC3") (pin "4") (pinfunction "SW1_4") (pintype "bidirectional"))
      (node (ref "L2") (pin "1") (pinfunction "1_1") (pintype "passive"))
    )
    (net (code "52") (name "Net-(IC3A-SW2)") (class "Default")
      (node (ref "IC3") (pin "2") (pinfunction "SW2_2") (pintype "bidirectional"))
      (node (ref "L2") (pin "2") (pinfunction "2_2") (pintype "passive"))
    )
    (net (code "53") (name "Net-(IC3A-SYNC)") (class "Default")
      (node (ref "IC3") (pin "7") (pinfunction "SYNC_7") (pintype "bidirectional"))
      (node (ref "R32") (pin "2") (pinfunction "2_2") (pintype "passive"))
      (node (ref "R33") (pin "2") (pinfunction "2_2") (pintype "passive"))
    )
    (net (code "54") (name "Net-(IC5-~{EN1})") (class "Default")
      (node (ref "IC5") (pin "3") (pinfunction "~{EN1}_3") (pintype "bidirectional"))
      (node (ref "R12") (pin "1") (pinfunction "1_1") (pintype "passive"))
    )
    (net (code "55") (name "Net-(IC5-~{EN2})") (class "Default")
      (node (ref "IC5") (pin "4") (pinfunction "~{EN2}_4") (pintype "bidirectional"))
      (node (ref "R11") (pin "1") (pinfunction "1_1") (pintype "passive"))
    )
    (net (code "56") (name "Net-(IC5-~{OC1})") (class "Default")
      (node (ref "IC5") (pin "8") (pinfunction "~{OC1}_8") (pintype "bidirectional"))
      (node (ref "R9") (pin "1") (pinfunction "1_1") (pintype "passive"))
    )
    (net (code "57") (name "Net-(IC5-~{OC2})") (class "Default")
      (node (ref "IC5") (pin "5") (pinfunction "~{OC2}_5") (pintype "bidirectional"))
      (node (ref "R10") (pin "1") (pinfunction "1_1") (pintype "passive"))
    )
    (net (code "58") (name "Net-(IC6-D+)") (class "Default")
      (node (ref "IC6") (pin "1") (pinfunction "D+P_1") (pintype "bidirectional"))
      (node (ref "IC6") (pin "6") (pinfunction "D+_6") (pintype "bidirectional"))
      (node (ref "IC7") (pin "14") (pinfunction "USBDP_14") (pintype "bidirectional"))
      (node (ref "J5") (pin "3") (pinfunction "D+_3") (pintype "passive"))
    )
    (net (code "59") (name "Net-(IC6-D-)") (class "Default")
      (node (ref "IC6") (pin "3") (pinfunction "D-P_3") (pintype "bidirectional"))
      (node (ref "IC6") (pin "4") (pinfunction "D-_4") (pintype "bidirectional"))
      (node (ref "IC7") (pin "15") (pinfunction "USBDM_15") (pintype "bidirectional"))
      (node (ref "J5") (pin "2") (pinfunction "D-_2") (pintype "passive"))
    )
    (net (code "60") (name "Net-(IC6-VCC)") (class "Default")
      (node (ref "C21") (pin "1") (pinfunction "1_1") (pintype "passive"))
      (node (ref "F1") (pin "1") (pinfunction "1_1") (pintype "passive"))
      (node (ref "IC6") (pin "5") (pinfunction "VCC_5") (pintype "bidirectional"))
      (node (ref "J5") (pin "1") (pinfunction "VBUS_1") (pintype "passive"))
    )
    (net (code "61") (name "Net-(IC7A-RXD)") (class "Default")
      (node (ref "IC7") (pin "2") (pinfunction "RXD_2") (pintype "input"))
      (node (ref "R15") (pin "2") (pinfunction "2_2") (pintype "passive"))
    )
    (net (code "62") (name "Net-(IC7A-TXD)") (class "Default")
      (node (ref "IC7") (pin "30") (pinfunction "TXD_30") (pintype "output"))
      (node (ref "IC8") (pin "2") (pinfunction "I_2") (pintype "input"))
    )
    (net (code "63") (name "Net-(IC8A-O)") (class "Default")
      (node (ref "IC8") (pin "6") (pinfunction "O_6") (pintype "tri_state"))
      (node (ref "R14") (pin "1") (pinfunction "1_1") (pintype "passive"))
    )
    (net (code "64") (name "Net-(IC8A-OE)") (class "Default")
      (node (ref "IC8") (pin "1") (pinfunction "OE_1") (pintype "input"))
      (node (ref "Q1") (pin "C") (pinfunction "C_C") (pintype "passive"))
      (node (ref "R16") (pin "1") (pinfunction "1_1") (pintype "passive"))
    )
    (net (code "65") (name "Net-(IC9A-O)") (class "Default")
      (node (ref "IC9") (pin "6") (pinfunction "O_6") (pintype "tri_state"))
      (node (ref "R15") (pin "1") (pinfunction "1_1") (pintype "passive"))
    )
    (net (code "66") (name "Net-(IC9A-OE)") (class "Default")
      (node (ref "IC9") (pin "1") (pinfunction "OE_1") (pintype "input"))
      (node (ref "Q2") (pin "C") (pinfunction "C_C") (pintype "passive"))
      (node (ref "R18") (pin "2") (pinfunction "2_2") (pintype "passive"))
    )
    (net (code "67") (name "Net-(IC9B-O)") (class "Default")
      (node (ref "IC9") (pin "3") (pinfunction "O_3") (pintype "tri_state"))
      (node (ref "R17") (pin "2") (pinfunction "2_2") (pintype "passive"))
    )
    (net (code "68") (name "Net-(IC10-CELL)") (class "Default")
      (node (ref "C26") (pin "1") (pinfunction "1_1") (pintype "passive"))
      (node (ref "IC10") (pin "2") (pinfunction "CELL_2") (pintype "bidirectional"))
      (node (ref "R21") (pin "2") (pinfunction "2_2") (pintype "passive"))
    )
    (net (code "69") (name "Net-(IC10-EO)") (class "Default")
      (node (ref "IC10") (pin "6") (pinfunction "EO_6") (pintype "bidirectional"))
      (node (ref "R28") (pin "1") (pinfunction "1_1") (pintype "passive"))
    )
    (net (code "70") (name "Net-(IC10-VDD)") (class "Default")
      (node (ref "C27") (pin "1") (pinfunction "1_1") (pintype "passive"))
      (node (ref "IC10") (pin "3") (pinfunction "VDD_3") (pintype "bidirectional"))
      (node (ref "R22") (pin "1") (pinfunction "1_1") (pintype "passive"))
    )
    (net (code "71") (name "Net-(IC12-FT{slash}OUT)") (class "Default")
      (node (ref "IC12") (pin "7") (pinfunction "FT/OUT_7") (pintype "bidirectional"))
      (node (ref "R29") (pin "1") (pinfunction "1_1") (pintype "passive"))
    )
    (net (code "72") (name "Net-(IC12-XI)") (class "Default")
      (node (ref "IC12") (pin "1") (pinfunction "XI_1") (pintype "bidirectional"))
      (node (ref "X1") (pin "2") (pinfunction "2_2") (pintype "passive"))
    )
    (net (code "73") (name "Net-(IC12-XO)") (class "Default")
      (node (ref "IC12") (pin "2") (pinfunction "XO_2") (pintype "bidirectional"))
      (node (ref "X1") (pin "1") (pinfunction "1_1") (pintype "passive"))
    )
    (net (code "74") (name "Net-(IC13-VOUT)") (class "Default")
      (node (ref "IC13") (pin "1") (pinfunction "VOUT_1") (pintype "bidirectional"))
      (node (ref "R19") (pin "2") (pinfunction "2_2") (pintype "passive"))
      (node (ref "R20") (pin "1") (pinfunction "1_1") (pintype "passive"))
    )
    (net (code "75") (name "Net-(IC14-VDD)") (class "Default")
      (node (ref "C31") (pin "1") (pinfunction "1_1") (pintype "passive"))
      (node (ref "C32") (pin "1") (pinfunction "1_1") (pintype "passive"))
      (node (ref "IC14") (pin "8") (pinfunction "VDD_8") (pintype "bidirectional"))
      (node (ref "L4") (pin "2") (pinfunction "2_2") (pintype "passive"))
    )
    (net (code "76") (name "Net-(IC14-VIN0)") (class "Default")
      (node (ref "IC14") (pin "3") (pinfunction "VIN0_3") (pintype "bidirectional"))
      (node (ref "J6") (pin "5") (pinfunction "5_5") (pintype "bidirectional"))
    )
    (net (code "77") (name "Net-(IC14-VIN1)") (class "Default")
      (node (ref "IC14") (pin "4") (pinfunction "VIN1_4") (pintype "bidirectional"))
      (node (ref "J6") (pin "4") (pinfunction "4_4") (pintype "bidirectional"))
    )
    (net (code "78") (name "Net-(IC14-VIN2)") (class "Default")
      (node (ref "IC14") (pin "5") (pinfunction "VIN2_5") (pintype "bidirectional"))
      (node (ref "J6") (pin "3") (pinfunction "3_3") (pintype "bidirectional"))
    )
    (net (code "79") (name "Net-(IC14-VIN3{slash}VREF)") (class "Default")
      (node (ref "IC14") (pin "6") (pinfunction "VIN3/VREF_6") (pintype "bidirectional"))
      (node (ref "J6") (pin "2") (pinfunction "2_2") (pintype "bidirectional"))
    )
    (net (code "80") (name "Net-(IC15A-O)") (class "Default")
      (node (ref "IC15") (pin "6") (pinfunction "O_6") (pintype "tri_state"))
      (node (ref "J11") (pin "1") (pinfunction "1_1") (pintype "bidirectional"))
    )
    (net (code "81") (name "Net-(J3-Pad31)") (class "Default")
      (node (ref "J3") (pin "31") (pinfunction "31_31") (pintype "bidirectional"))
      (node (ref "R26") (pin "1") (pinfunction "1_1") (pintype "passive"))
    )
    (net (code "82") (name "Net-(J3-Pad33)") (class "Default")
      (node (ref "J3") (pin "33") (pinfunction "33_33") (pintype "bidirectional"))
      (node (ref "R27") (pin "1") (pinfunction "1_1") (pintype "passive"))
    )
    (net (code "83") (name "Net-(LED1-PadC)") (class "Default")
      (node (ref "LED1") (pin "C") (pinfunction "C_C") (pintype "passive"))
      (node (ref "R23") (pin "2") (pinfunction "2_2") (pintype "passive"))
    )
    (net (code "84") (name "Net-(LED2-PadC)") (class "Default")
      (node (ref "LED2") (pin "C") (pinfunction "C_C") (pintype "passive"))
      (node (ref "R24") (pin "2") (pinfunction "2_2") (pintype "passive"))
    )
    (net (code "85") (name "Net-(LED3-PadC)") (class "Default")
      (node (ref "LED3") (pin "C") (pinfunction "C_C") (pintype "passive"))
      (node (ref "R25") (pin "2") (pinfunction "2_2") (pintype "passive"))
    )
    (net (code "86") (name "Net-(LED4-PadC)") (class "Default")
      (node (ref "LED4") (pin "C") (pinfunction "C_C") (pintype "passive"))
      (node (ref "R35") (pin "2") (pinfunction "2_2") (pintype "passive"))
    )
    (net (code "87") (name "Net-(MICROSD-PadCD1)") (class "Default")
      (node (ref "MICROSD") (pin "CD1") (pinfunction "CD1_CD1") (pintype "bidirectional"))
      (node (ref "TP3") (pin "TP") (pinfunction "TP_TP") (pintype "input"))
    )
    (net (code "88") (name "Net-(MICROSD-PadCD2)") (class "Default")
      (node (ref "MICROSD") (pin "CD2") (pinfunction "CD2_CD2") (pintype "bidirectional"))
      (node (ref "TP4") (pin "TP") (pinfunction "TP_TP") (pintype "input"))
    )
    (net (code "89") (name "Net-(NTC1-Pad1)") (class "Default")
      (node (ref "NTC1") (pin "1") (pinfunction "1_1") (pintype "passive"))
      (node (ref "R40") (pin "1") (pinfunction "1_1") (pintype "passive"))
      (node (ref "TP1") (pin "TP") (pinfunction "TP_TP") (pintype "input"))
    )
    (net (code "90") (name "Net-(Q2-PadB)") (class "Default")
      (node (ref "Q2") (pin "B") (pinfunction "B_B") (pintype "passive"))
      (node (ref "R19") (pin "1") (pinfunction "1_1") (pintype "passive"))
    )
    (net (code "91") (name "PWEN") (class "Default")
      (node (ref "IC2") (pin "6") (pinfunction "EN_6") (pintype "bidirectional"))
      (node (ref "IC3") (pin "6") (pinfunction "EN_6") (pintype "bidirectional"))
      (node (ref "J13") (pin "2") (pinfunction "2_2") (pintype "bidirectional"))
    )
    (net (code "92") (name "RTS1") (class "Default")
      (node (ref "J3") (pin "8") (pinfunction "8_8") (pintype "bidirectional"))
      (node (ref "J7") (pin "4") (pinfunction "4_4") (pintype "bidirectional"))
    )
    (net (code "93") (name "RTS2") (class "Default")
      (node (ref "J3") (pin "26") (pinfunction "26_26") (pintype "bidirectional"))
      (node (ref "J8") (pin "4") (pinfunction "4_4") (pintype "bidirectional"))
    )
    (net (code "94") (name "RX1") (class "Default")
      (node (ref "J3") (pin "10") (pinfunction "10_10") (pintype "bidirectional"))
      (node (ref "J7") (pin "5") (pinfunction "5_5") (pintype "bidirectional"))
    )
    (net (code "95") (name "RX2") (class "Default")
      (node (ref "J3") (pin "28") (pinfunction "28_28") (pintype "bidirectional"))
      (node (ref "J8") (pin "5") (pinfunction "5_5") (pintype "bidirectional"))
    )
    (net (code "96") (name "SPI1_CLK") (class "Default")
      (node (ref "J10") (pin "2") (pinfunction "2_2") (pintype "bidirectional"))
      (node (ref "J3") (pin "45") (pinfunction "45_45") (pintype "bidirectional"))
      (node (ref "MICROSD") (pin "5") (pinfunction "CLK_5") (pintype "bidirectional"))
    )
    (net (code "97") (name "SPI1_MISO") (class "Default")
      (node (ref "J10") (pin "5") (pinfunction "5_5") (pintype "bidirectional"))
      (node (ref "J3") (pin "39") (pinfunction "39_39") (pintype "bidirectional"))
      (node (ref "MICROSD") (pin "7") (pinfunction "DO_7") (pintype "bidirectional"))
    )
    (net (code "98") (name "SPI1_MOSI") (class "Default")
      (node (ref "J10") (pin "3") (pinfunction "3_3") (pintype "bidirectional"))
      (node (ref "J3") (pin "43") (pinfunction "43_43") (pintype "bidirectional"))
      (node (ref "MICROSD") (pin "3") (pinfunction "DI_3") (pintype "bidirectional"))
    )
    (net (code "99") (name "SUSP") (class "Default")
      (node (ref "IC1") (pin "7") (pinfunction "SUSP_7") (pintype "bidirectional"))
      (node (ref "IC7") (pin "11") (pinfunction "CBUS3_11") (pintype "bidirectional"))
      (node (ref "R36") (pin "1") (pinfunction "1_1") (pintype "passive"))
    )
    (net (code "100") (name "TX1") (class "Default")
      (node (ref "J3") (pin "6") (pinfunction "6_6") (pintype "bidirectional"))
      (node (ref "J7") (pin "6") (pinfunction "6_6") (pintype "bidirectional"))
    )
    (net (code "101") (name "TX2") (class "Default")
      (node (ref "J3") (pin "24") (pinfunction "24_24") (pintype "bidirectional"))
      (node (ref "J8") (pin "6") (pinfunction "6_6") (pintype "bidirectional"))
    )
    (net (code "102") (name "VBAT") (class "Default")
      (node (ref "C15") (pin "1") (pinfunction "1_1") (pintype "passive"))
      (node (ref "D4") (pin "A") (pinfunction "A_A") (pintype "passive"))
      (node (ref "IC1") (pin "2") (pinfunction "BAT_2") (pintype "bidirectional"))
      (node (ref "IC12") (pin "3") (pinfunction "VBAT_3") (pintype "bidirectional"))
      (node (ref "J1") (pin "1") (pinfunction "1_1") (pintype "bidirectional"))
      (node (ref "R21") (pin "1") (pinfunction "1_1") (pintype "passive"))
      (node (ref "R22") (pin "2") (pinfunction "2_2") (pintype "passive"))
    )
    (net (code "103") (name "VBUS") (class "Default")
      (node (ref "C3") (pin "+") (pinfunction "+_+") (pintype "passive"))
      (node (ref "C38") (pin "1") (pinfunction "1_1") (pintype "passive"))
      (node (ref "D1") (pin "C") (pinfunction "C_C") (pintype "passive"))
      (node (ref "IC1") (pin "3") (pinfunction "OUT_3") (pintype "bidirectional"))
      (node (ref "J13") (pin "3") (pinfunction "3_3") (pintype "bidirectional"))
      (node (ref "L6") (pin "2") (pinfunction "2_2") (pintype "passive"))
      (node (ref "L7") (pin "1") (pinfunction "1_1") (pintype "passive"))
      (node (ref "LED1") (pin "A") (pinfunction "A_A") (pintype "passive"))
      (node (ref "LED2") (pin "A") (pinfunction "A_A") (pintype "passive"))
    )
    (net (code "104") (name "VUSB_3V3") (class "Default")
      (node (ref "C24") (pin "1") (pinfunction "1_1") (pintype "passive"))
      (node (ref "C30") (pin "1") (pinfunction "1_1") (pintype "passive"))
      (node (ref "C33") (pin "1") (pinfunction "1_1") (pintype "passive"))
      (node (ref "IC13") (pin "3") (pinfunction "VIN_3") (pintype "bidirectional"))
      (node (ref "IC7") (pin "1") (pinfunction "VCCIO_1") (pintype "power_in"))
      (node (ref "IC7") (pin "16") (pinfunction "3V3OUT_16") (pintype "output"))
      (node (ref "IC8") (pin "8") (pinfunction "VCC_8") (pintype "power_in"))
      (node (ref "R16") (pin "2") (pinfunction "2_2") (pintype "passive"))
      (node (ref "R20") (pin "2") (pinfunction "2_2") (pintype "passive"))
      (node (ref "R36") (pin "2") (pinfunction "2_2") (pintype "passive"))
    )
    (net (code "105") (name "VUSB_DEB") (class "Default")
      (node (ref "C1") (pin "1") (pinfunction "1_1") (pintype "passive"))
      (node (ref "C22") (pin "1") (pinfunction "1_1") (pintype "passive"))
      (node (ref "C23") (pin "1") (pinfunction "1_1") (pintype "passive"))
      (node (ref "D3") (pin "A") (pinfunction "A_A") (pintype "passive"))
      (node (ref "IC1") (pin "1") (pinfunction "IN2_1") (pintype "bidirectional"))
      (node (ref "IC1") (pin "4") (pinfunction "IN1_4") (pintype "bidirectional"))
      (node (ref "IC7") (pin "19") (pinfunction "VCC_19") (pintype "power_in"))
      (node (ref "L5") (pin "2") (pinfunction "2_2") (pintype "passive"))
    )
    (net (code "106") (name "VWALL") (class "Default")
      (node (ref "C16") (pin "1") (pinfunction "1_1") (pintype "passive"))
      (node (ref "D1") (pin "A") (pinfunction "A_A") (pintype "passive"))
      (node (ref "D2") (pin "A") (pinfunction "A_A") (pintype "passive"))
      (node (ref "J2") (pin "1") (pinfunction "1_1") (pintype "passive"))
      (node (ref "R1") (pin "2") (pinfunction "2_2") (pintype "passive"))
    )
    (net (code "107") (name "WKUP") (class "Default")
      (node (ref "J12") (pin "4") (pinfunction "4_4") (pintype "bidirectional"))
      (node (ref "J3") (pin "46") (pinfunction "46_46") (pintype "bidirectional"))
    )
    (net (code "108") (name "WLNK") (class "Default")
      (node (ref "IC15") (pin "3") (pinfunction "O_3") (pintype "tri_state"))
      (node (ref "J12") (pin "2") (pinfunction "2_2") (pintype "bidirectional"))
      (node (ref "R25") (pin "1") (pinfunction "1_1") (pintype "passive"))
    )
    (net (code "109") (name "W_LINKLED") (class "Default")
      (node (ref "IC15") (pin "5") (pinfunction "I_5") (pintype "input"))
      (node (ref "J3") (pin "25") (pinfunction "25_25") (pintype "bidirectional"))
      (node (ref "R34") (pin "1") (pinfunction "1_1") (pintype "passive"))
    )
    (net (code "110") (name "unconnected-(IC5-OUT2-Pad6)") (class "Default")
      (node (ref "IC5") (pin "6") (pinfunction "OUT2_6") (pintype "bidirectional"))
    )
    (net (code "111") (name "unconnected-(IC7A-CBUS0-Pad22)") (class "Default")
      (node (ref "IC7") (pin "22") (pinfunction "CBUS0_22") (pintype "bidirectional"))
    )
    (net (code "112") (name "unconnected-(IC7A-CBUS1-Pad21)") (class "Default")
      (node (ref "IC7") (pin "21") (pinfunction "CBUS1_21") (pintype "bidirectional"))
    )
    (net (code "113") (name "unconnected-(IC7A-CBUS2-Pad10)") (class "Default")
      (node (ref "IC7") (pin "10") (pinfunction "CBUS2_10") (pintype "bidirectional"))
    )
    (net (code "114") (name "unconnected-(IC7A-CBUS4-Pad9)") (class "Default")
      (node (ref "IC7") (pin "9") (pinfunction "CBUS4_9") (pintype "bidirectional"))
    )
    (net (code "115") (name "unconnected-(IC7A-OSCI-Pad27)") (class "Default")
      (node (ref "IC7") (pin "27") (pinfunction "OSCI_27") (pintype "input"))
    )
    (net (code "116") (name "unconnected-(IC7A-OSCO-Pad28)") (class "Default")
      (node (ref "IC7") (pin "28") (pinfunction "OSCO_28") (pintype "output"))
    )
    (net (code "117") (name "unconnected-(IC7A-~{CTS}-Pad8)") (class "Default")
      (node (ref "IC7") (pin "8") (pinfunction "~{CTS}_8") (pintype "input"))
    )
    (net (code "118") (name "unconnected-(IC7A-~{DCD}-Pad7)") (class "Default")
      (node (ref "IC7") (pin "7") (pinfunction "~{DCD}_7") (pintype "input"))
    )
    (net (code "119") (name "unconnected-(IC7A-~{DSR}-Pad6)") (class "Default")
      (node (ref "IC7") (pin "6") (pinfunction "~{DSR}_6") (pintype "input"))
    )
    (net (code "120") (name "unconnected-(IC7A-~{DTR}-Pad31)") (class "Default")
      (node (ref "IC7") (pin "31") (pinfunction "~{DTR}_31") (pintype "output"))
    )
    (net (code "121") (name "unconnected-(IC7A-~{RESET}-Pad18)") (class "Default")
      (node (ref "IC7") (pin "18") (pinfunction "~{RESET}_18") (pintype "input"))
    )
    (net (code "122") (name "unconnected-(IC7A-~{RI}-Pad3)") (class "Default")
      (node (ref "IC7") (pin "3") (pinfunction "~{RI}_3") (pintype "input"))
    )
    (net (code "123") (name "unconnected-(IC7A-~{RTS}-Pad32)") (class "Default")
      (node (ref "IC7") (pin "32") (pinfunction "~{RTS}_32") (pintype "output"))
    )
    (net (code "124") (name "unconnected-(IC8B-O-Pad3)") (class "Default")
      (node (ref "IC8") (pin "3") (pinfunction "O_3") (pintype "tri_state"))
    )
    (net (code "125") (name "unconnected-(IC11-INT-Pad5)") (class "Default")
      (node (ref "IC11") (pin "5") (pinfunction "INT_5") (pintype "bidirectional"))
    )
    (net (code "126") (name "unconnected-(IC11-T_CRIT-Pad3)") (class "Default")
      (node (ref "IC11") (pin "3") (pinfunction "T_CRIT_3") (pintype "bidirectional"))
    )
    (net (code "127") (name "unconnected-(J2-Pad2)") (class "Default")
      (node (ref "J2") (pin "2") (pinfunction "2_2") (pintype "passive"))
    )
    (net (code "128") (name "unconnected-(J3-Pad3)") (class "Default")
      (node (ref "J3") (pin "3") (pinfunction "3_3") (pintype "bidirectional"))
    )
    (net (code "129") (name "unconnected-(J3-Pad5)") (class "Default")
      (node (ref "J3") (pin "5") (pinfunction "5_5") (pintype "bidirectional"))
    )
    (net (code "130") (name "unconnected-(J3-Pad21)") (class "Default")
      (node (ref "J3") (pin "21") (pinfunction "21_21") (pintype "bidirectional"))
    )
    (net (code "131") (name "unconnected-(J3-Pad23)") (class "Default")
      (node (ref "J3") (pin "23") (pinfunction "23_23") (pintype "bidirectional"))
    )
    (net (code "132") (name "unconnected-(J3-Pad29)") (class "Default")
      (node (ref "J3") (pin "29") (pinfunction "29_29") (pintype "bidirectional"))
    )
    (net (code "133") (name "unconnected-(J3-Pad49)") (class "Default")
      (node (ref "J3") (pin "49") (pinfunction "49_49") (pintype "bidirectional"))
    )
    (net (code "134") (name "unconnected-(J3-Pad51)") (class "Default")
      (node (ref "J3") (pin "51") (pinfunction "51_51") (pintype "bidirectional"))
    )
    (net (code "135") (name "unconnected-(J3-Pad56)") (class "Default")
      (node (ref "J3") (pin "56") (pinfunction "56_56") (pintype "bidirectional"))
    )
    (net (code "136") (name "unconnected-(J3-Pad58)") (class "Default")
      (node (ref "J3") (pin "58") (pinfunction "58_58") (pintype "bidirectional"))
    )
    (net (code "137") (name "unconnected-(J3-Pad62)") (class "Default")
      (node (ref "J3") (pin "62") (pinfunction "62_62") (pintype "bidirectional"))
    )
    (net (code "138") (name "unconnected-(J3-Pad63)") (class "Default")
      (node (ref "J3") (pin "63") (pinfunction "63_63") (pintype "bidirectional"))
    )
    (net (code "139") (name "unconnected-(J3-Pad64)") (class "Default")
      (node (ref "J3") (pin "64") (pinfunction "64_64") (pintype "bidirectional"))
    )
    (net (code "140") (name "unconnected-(J3-Pad65)") (class "Default")
      (node (ref "J3") (pin "65") (pinfunction "65_65") (pintype "bidirectional"))
    )
    (net (code "141") (name "unconnected-(J3-Pad68)") (class "Default")
      (node (ref "J3") (pin "68") (pinfunction "68_68") (pintype "bidirectional"))
    )
    (net (code "142") (name "unconnected-(J3-Pad69)") (class "Default")
      (node (ref "J3") (pin "69") (pinfunction "69_69") (pintype "bidirectional"))
    )
    (net (code "143") (name "unconnected-(J3-Pad70)") (class "Default")
      (node (ref "J3") (pin "70") (pinfunction "70_70") (pintype "bidirectional"))
    )
    (net (code "144") (name "unconnected-(J3-Pad71)") (class "Default")
      (node (ref "J3") (pin "71") (pinfunction "71_71") (pintype "bidirectional"))
    )
    (net (code "145") (name "unconnected-(J3-Pad75)") (class "Default")
      (node (ref "J3") (pin "75") (pinfunction "75_75") (pintype "bidirectional"))
    )
    (net (code "146") (name "unconnected-(J3-Pad77)") (class "Default")
      (node (ref "J3") (pin "77") (pinfunction "77_77") (pintype "bidirectional"))
    )
    (net (code "147") (name "unconnected-(J5-NC-Pad4)") (class "Default")
      (node (ref "J5") (pin "4") (pinfunction "NC_4") (pintype "passive"))
    )
    (net (code "148") (name "unconnected-(J6-Pad6)") (class "Default")
      (node (ref "J6") (pin "6") (pinfunction "6_6") (pintype "bidirectional"))
    )
    (net (code "149") (name "unconnected-(J11-Pad6)") (class "Default")
      (node (ref "J11") (pin "6") (pinfunction "6_6") (pintype "bidirectional"))
    )
    (net (code "150") (name "unconnected-(J12-Pad3)") (class "Default")
      (node (ref "J12") (pin "3") (pinfunction "3_3") (pintype "bidirectional"))
    )
    (net (code "151") (name "unconnected-(MICROSD-NC-Pad1)") (class "Default")
      (node (ref "MICROSD") (pin "1") (pinfunction "NC_1") (pintype "bidirectional"))
    )
    (net (code "152") (name "unconnected-(MICROSD-RSV-Pad8)") (class "Default")
      (node (ref "MICROSD") (pin "8") (pinfunction "RSV_8") (pintype "bidirectional"))
    )
  )
)
